# wiiceiver_v2.net
KiCad netlist of a schematic drawn in EAGLE
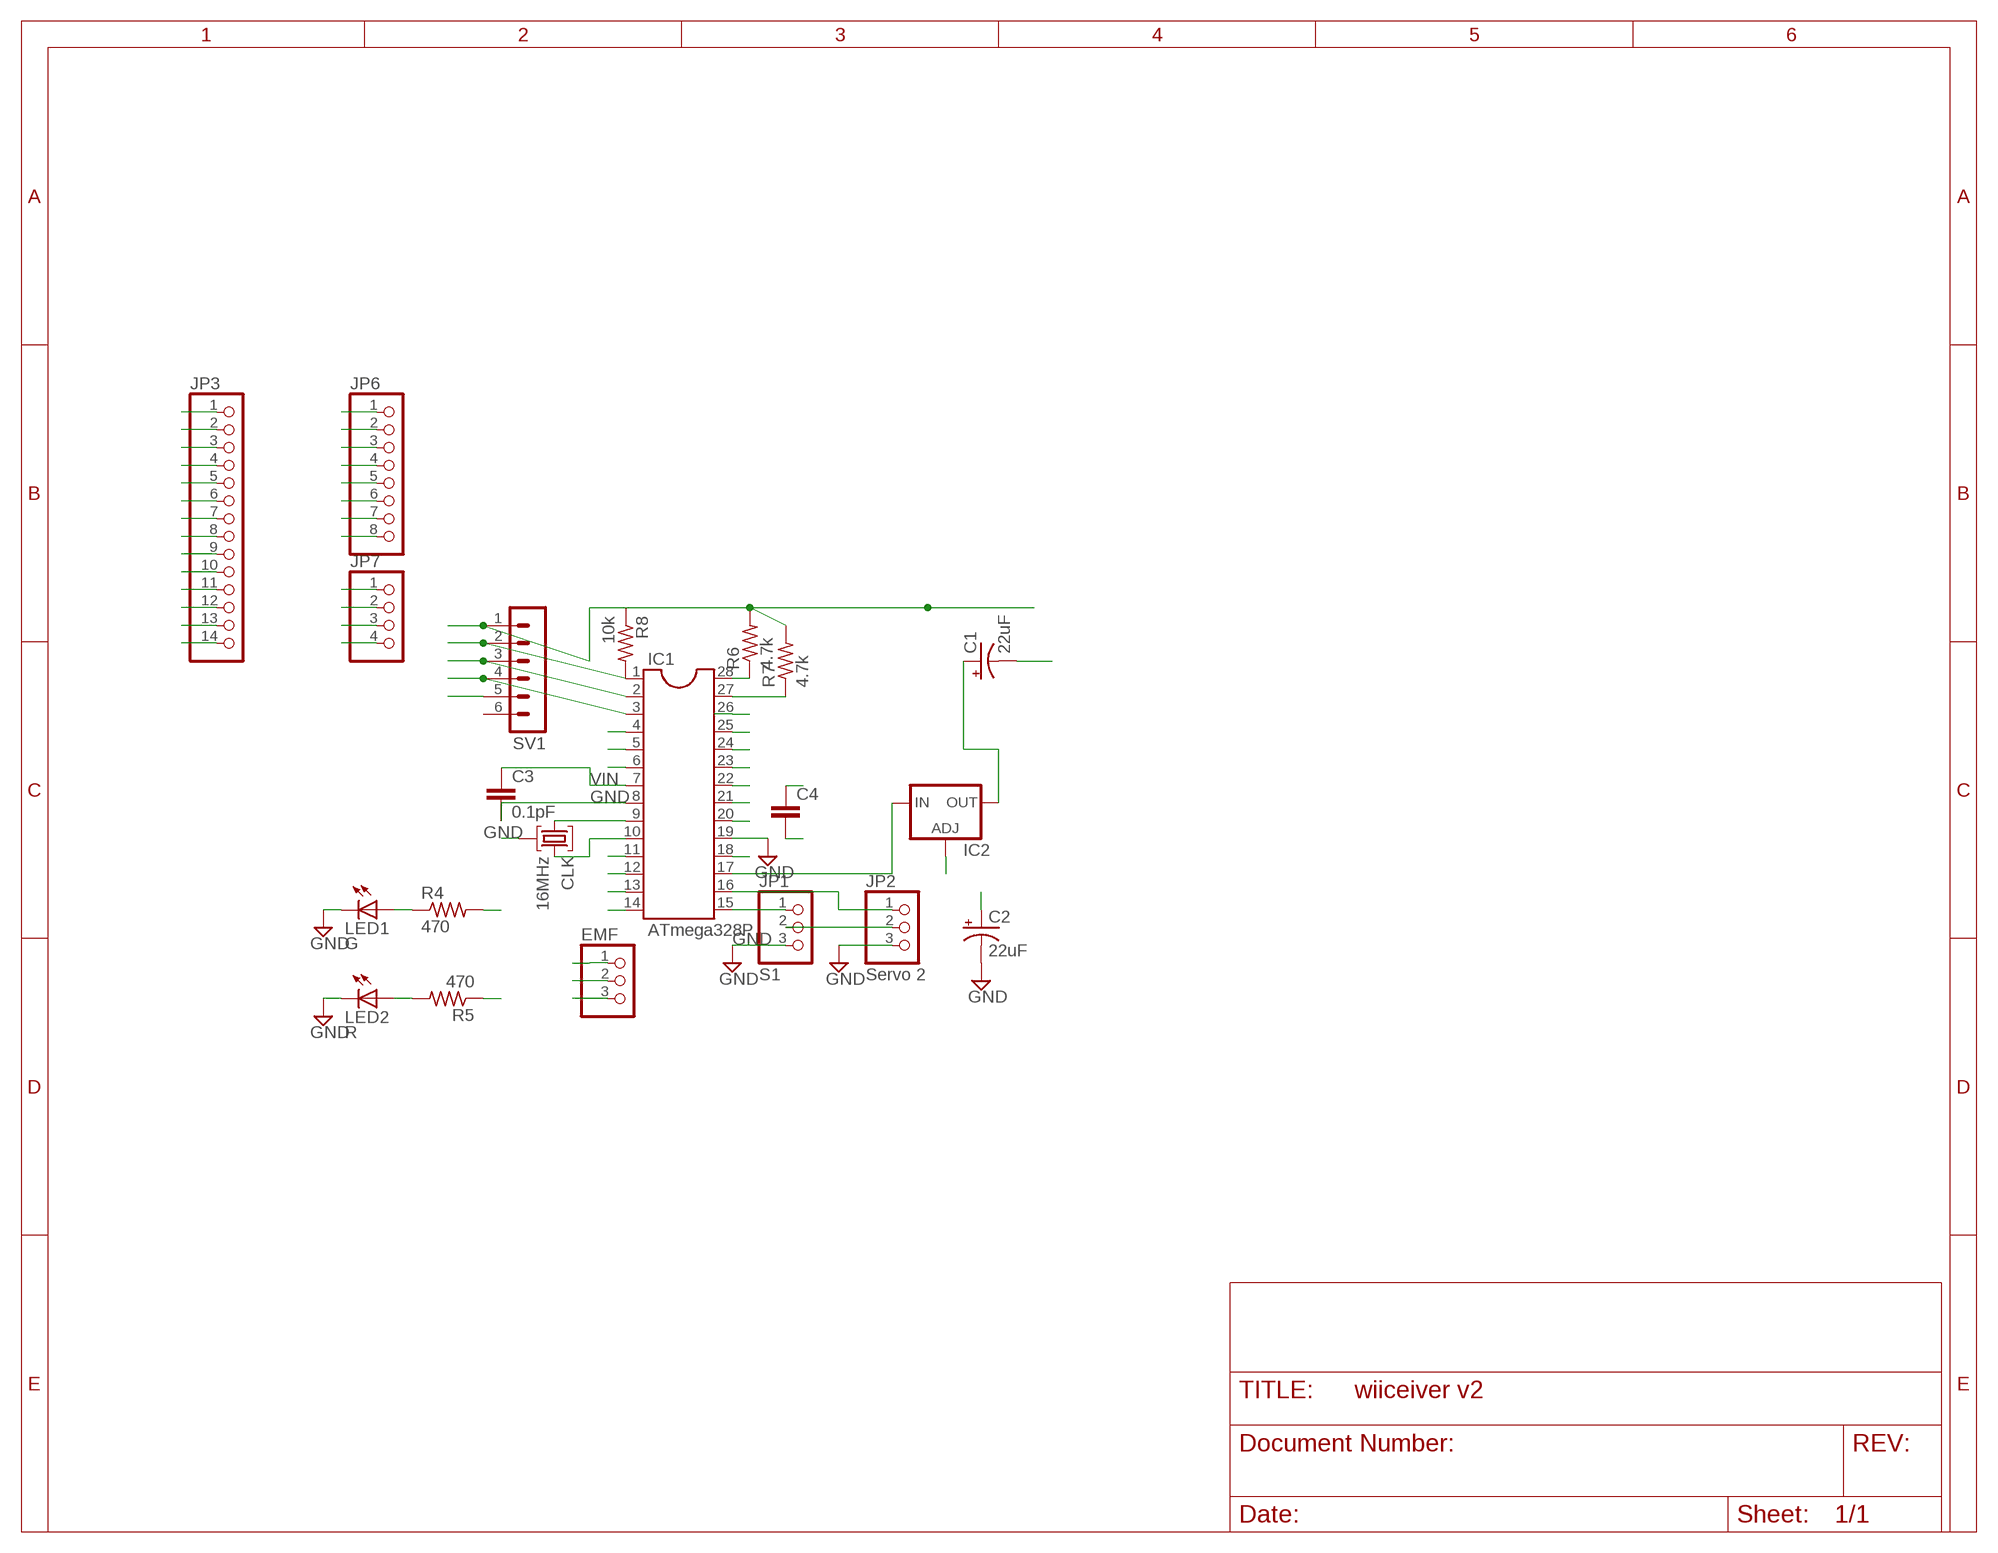
[diagram p0: schematic, sheet 1]

(export (version "E")
  (design (tool "Eeschema 10.0.6"))
  (components
    (comp (ref "C1")
      (value "22uF")
      (footprint "eagle-import:B45181A")
      (libsource (lib "eagle-import") (part "CPOL-USB45181A"))
    )
    (comp (ref "C2")
      (value "22uF")
      (footprint "eagle-import:B45181A")
      (libsource (lib "eagle-import") (part "CPOL-USB45181A"))
    )
    (comp (ref "C3")
      (value "0.1pF")
      (footprint "eagle-import:C5B2.5")
      (libsource (lib "eagle-import") (part "C5/2.5"))
    )
    (comp (ref "C4")
      (value "C5/2.5")
      (footprint "eagle-import:C5B2.5")
      (libsource (lib "eagle-import") (part "C5/2.5"))
    )
    (comp (ref "CLK")
      (value "16MHz")
      (footprint "eagle-import:HC49U")
      (libsource (lib "eagle-import") (part "IXFA"))
    )
    (comp (ref "EMF")
      (value "PINHD-1X3")
      (footprint "eagle-import:1X03")
      (libsource (lib "eagle-import") (part "PINHD-1X3"))
    )
    (comp (ref "IC1")
      (value "ATmega328P")
      (footprint "eagle-import:DIL28-3")
      (libsource (lib "eagle-import") (part "DIL28-3"))
    )
    (comp (ref "IC2")
      (value "LM317TS")
      (footprint "eagle-import:317TS")
      (libsource (lib "eagle-import") (part "LM317TS"))
    )
    (comp (ref "JP1")
      (value "S1")
      (footprint "eagle-import:1X03")
      (libsource (lib "eagle-import") (part "PINHD-1X3"))
    )
    (comp (ref "JP2")
      (value "Servo 2")
      (footprint "eagle-import:1X03")
      (libsource (lib "eagle-import") (part "PINHD-1X3"))
    )
    (comp (ref "JP3")
      (value "PINHD-1X14")
      (footprint "eagle-import:1X14")
      (libsource (lib "eagle-import") (part "PINHD-1X14"))
    )
    (comp (ref "JP6")
      (value "PINHD-1X8")
      (footprint "eagle-import:1X08")
      (libsource (lib "eagle-import") (part "PINHD-1X8"))
    )
    (comp (ref "JP7")
      (value "PINHD-1X4")
      (footprint "eagle-import:1X04")
      (libsource (lib "eagle-import") (part "PINHD-1X4"))
    )
    (comp (ref "LED1")
      (value "G")
      (footprint "eagle-import:LED3MM")
      (libsource (lib "eagle-import") (part "LED3MM"))
    )
    (comp (ref "LED2")
      (value "R")
      (footprint "eagle-import:LED3MM")
      (libsource (lib "eagle-import") (part "LED3MM"))
    )
    (comp (ref "R4")
      (value "470")
      (footprint "eagle-import:0204V")
      (libsource (lib "eagle-import") (part "R-US_0204/2V"))
    )
    (comp (ref "R5")
      (value "470")
      (footprint "eagle-import:0204V")
      (libsource (lib "eagle-import") (part "R-US_0204/2V"))
    )
    (comp (ref "R6")
      (value "4.7k")
      (footprint "eagle-import:0204V")
      (libsource (lib "eagle-import") (part "R-US_0204/2V"))
    )
    (comp (ref "R7")
      (value "4.7k")
      (footprint "eagle-import:0204V")
      (libsource (lib "eagle-import") (part "R-US_0204/2V"))
    )
    (comp (ref "R8")
      (value "10k")
      (footprint "eagle-import:0204V")
      (libsource (lib "eagle-import") (part "R-US_0204/2V"))
    )
    (comp (ref "SV1")
      (value "MA06-1")
      (footprint "eagle-import:MA06-1")
      (libsource (lib "eagle-import") (part "MA06-1"))
    )
  )
  (nets
    (net (code "1") (name "/A0") (class "Default")
      (node (ref "IC1") (pin "23") (pinfunction "23_23") (pintype "passive"))
      (node (ref "JP3") (pin "6") (pinfunction "6_6") (pintype "passive"))
    )
    (net (code "2") (name "/A1") (class "Default")
      (node (ref "IC1") (pin "24") (pinfunction "24_24") (pintype "passive"))
      (node (ref "JP3") (pin "5") (pinfunction "5_5") (pintype "passive"))
    )
    (net (code "3") (name "/A2") (class "Default")
      (node (ref "IC1") (pin "25") (pinfunction "25_25") (pintype "passive"))
      (node (ref "JP3") (pin "4") (pinfunction "4_4") (pintype "passive"))
    )
    (net (code "4") (name "/A3") (class "Default")
      (node (ref "IC1") (pin "26") (pinfunction "26_26") (pintype "passive"))
      (node (ref "JP3") (pin "3") (pinfunction "3_3") (pintype "passive"))
    )
    (net (code "5") (name "/A4") (class "Default")
      (node (ref "IC1") (pin "27") (pinfunction "27_27") (pintype "passive"))
      (node (ref "JP3") (pin "2") (pinfunction "2_2") (pintype "passive"))
      (node (ref "R7") (pin "1") (pinfunction "1_1") (pintype "passive"))
    )
    (net (code "6") (name "/A5") (class "Default")
      (node (ref "IC1") (pin "28") (pinfunction "28_28") (pintype "passive"))
      (node (ref "JP3") (pin "1") (pinfunction "1_1") (pintype "passive"))
      (node (ref "R6") (pin "1") (pinfunction "1_1") (pintype "passive"))
    )
    (net (code "7") (name "/D0") (class "Default")
      (node (ref "IC1") (pin "2") (pinfunction "2_2") (pintype "passive"))
      (node (ref "JP6") (pin "2") (pinfunction "2_2") (pintype "passive"))
      (node (ref "SV1") (pin "3") (pinfunction "3_3") (pintype "passive"))
    )
    (net (code "8") (name "/D1") (class "Default")
      (node (ref "IC1") (pin "3") (pinfunction "3_3") (pintype "passive"))
      (node (ref "JP6") (pin "3") (pinfunction "3_3") (pintype "passive"))
      (node (ref "SV1") (pin "4") (pinfunction "4_4") (pintype "passive"))
    )
    (net (code "9") (name "/D2") (class "Default")
      (node (ref "IC1") (pin "4") (pinfunction "4_4") (pintype "passive"))
      (node (ref "JP6") (pin "4") (pinfunction "4_4") (pintype "passive"))
    )
    (net (code "10") (name "/D3") (class "Default")
      (node (ref "IC1") (pin "5") (pinfunction "5_5") (pintype "passive"))
      (node (ref "JP6") (pin "5") (pinfunction "5_5") (pintype "passive"))
    )
    (net (code "11") (name "/D4") (class "Default")
      (node (ref "IC1") (pin "6") (pinfunction "6_6") (pintype "passive"))
      (node (ref "JP6") (pin "6") (pinfunction "6_6") (pintype "passive"))
    )
    (net (code "12") (name "/D5") (class "Default")
      (node (ref "IC1") (pin "11") (pinfunction "11_11") (pintype "passive"))
      (node (ref "JP7") (pin "1") (pinfunction "1_1") (pintype "passive"))
    )
    (net (code "13") (name "/D6") (class "Default")
      (node (ref "IC1") (pin "12") (pinfunction "12_12") (pintype "passive"))
      (node (ref "JP7") (pin "2") (pinfunction "2_2") (pintype "passive"))
      (node (ref "R4") (pin "2") (pinfunction "2_2") (pintype "passive"))
    )
    (net (code "14") (name "/D7") (class "Default")
      (node (ref "IC1") (pin "13") (pinfunction "13_13") (pintype "passive"))
      (node (ref "JP7") (pin "3") (pinfunction "3_3") (pintype "passive"))
    )
    (net (code "15") (name "/D8") (class "Default")
      (node (ref "IC1") (pin "14") (pinfunction "14_14") (pintype "passive"))
      (node (ref "JP7") (pin "4") (pinfunction "4_4") (pintype "passive"))
      (node (ref "R5") (pin "1") (pinfunction "1_1") (pintype "passive"))
    )
    (net (code "16") (name "/D9") (class "Default")
      (node (ref "IC1") (pin "15") (pinfunction "15_15") (pintype "passive"))
      (node (ref "JP1") (pin "1") (pinfunction "1_1") (pintype "passive"))
      (node (ref "JP3") (pin "14") (pinfunction "14_14") (pintype "passive"))
    )
    (net (code "17") (name "/D10") (class "Default")
      (node (ref "IC1") (pin "16") (pinfunction "16_16") (pintype "passive"))
      (node (ref "JP2") (pin "1") (pinfunction "1_1") (pintype "passive"))
      (node (ref "JP3") (pin "13") (pinfunction "13_13") (pintype "passive"))
    )
    (net (code "18") (name "/D11") (class "Default")
      (node (ref "IC1") (pin "17") (pinfunction "17_17") (pintype "passive"))
      (node (ref "IC2") (pin "3") (pinfunction "IN_3") (pintype "input"))
      (node (ref "JP3") (pin "12") (pinfunction "12_12") (pintype "passive"))
    )
    (net (code "19") (name "/D12") (class "Default")
      (node (ref "IC1") (pin "18") (pinfunction "18_18") (pintype "passive"))
      (node (ref "JP3") (pin "11") (pinfunction "11_11") (pintype "passive"))
    )
    (net (code "20") (name "/RST") (class "Default")
      (node (ref "IC1") (pin "1") (pinfunction "1_1") (pintype "passive"))
      (node (ref "JP6") (pin "1") (pinfunction "1_1") (pintype "passive"))
      (node (ref "R8") (pin "2") (pinfunction "2_2") (pintype "passive"))
      (node (ref "SV1") (pin "2") (pinfunction "2_2") (pintype "passive"))
    )
    (net (code "21") (name "/VIN") (class "Default")
      (node (ref "C3") (pin "1") (pinfunction "1_1") (pintype "passive"))
      (node (ref "C4") (pin "1") (pinfunction "1_1") (pintype "passive"))
      (node (ref "EMF") (pin "3") (pinfunction "3_3") (pintype "passive"))
      (node (ref "IC1") (pin "20") (pinfunction "20_20") (pintype "passive"))
      (node (ref "IC1") (pin "21") (pinfunction "21_21") (pintype "passive"))
      (node (ref "IC1") (pin "7") (pinfunction "7_7") (pintype "passive"))
      (node (ref "JP3") (pin "8") (pinfunction "8_8") (pintype "passive"))
      (node (ref "JP3") (pin "9") (pinfunction "9_9") (pintype "passive"))
      (node (ref "JP6") (pin "7") (pinfunction "7_7") (pintype "passive"))
      (node (ref "R6") (pin "2") (pinfunction "2_2") (pintype "passive"))
      (node (ref "R7") (pin "2") (pinfunction "2_2") (pintype "passive"))
      (node (ref "R8") (pin "1") (pinfunction "1_1") (pintype "passive"))
      (node (ref "SV1") (pin "1") (pinfunction "1_1") (pintype "passive"))
    )
    (net (code "22") (name "/VRAW") (class "Default")
      (node (ref "C2") (pin "+") (pinfunction "+_+") (pintype "passive"))
      (node (ref "EMF") (pin "1") (pinfunction "1_1") (pintype "passive"))
      (node (ref "JP1") (pin "2") (pinfunction "2_2") (pintype "passive"))
      (node (ref "JP2") (pin "2") (pinfunction "2_2") (pintype "passive"))
    )
    (net (code "23") (name "GND") (class "Default")
      (node (ref "C1") (pin "-") (pinfunction "-_-") (pintype "passive"))
      (node (ref "C2") (pin "-") (pinfunction "-_-") (pintype "passive"))
      (node (ref "C3") (pin "2") (pinfunction "2_2") (pintype "passive"))
      (node (ref "C4") (pin "2") (pinfunction "2_2") (pintype "passive"))
      (node (ref "CLK") (pin "2") (pinfunction "2_2") (pintype "passive"))
      (node (ref "EMF") (pin "2") (pinfunction "2_2") (pintype "passive"))
      (node (ref "IC1") (pin "19") (pinfunction "19_19") (pintype "passive"))
      (node (ref "IC1") (pin "22") (pinfunction "22_22") (pintype "passive"))
      (node (ref "IC1") (pin "8") (pinfunction "8_8") (pintype "passive"))
      (node (ref "IC2") (pin "1") (pinfunction "ADJ_1") (pintype "input"))
      (node (ref "JP1") (pin "3") (pinfunction "3_3") (pintype "passive"))
      (node (ref "JP2") (pin "3") (pinfunction "3_3") (pintype "passive"))
      (node (ref "JP3") (pin "7") (pinfunction "7_7") (pintype "passive"))
      (node (ref "JP6") (pin "8") (pinfunction "8_8") (pintype "passive"))
      (node (ref "LED1") (pin "K") (pinfunction "C_K") (pintype "passive"))
      (node (ref "LED2") (pin "K") (pinfunction "C_K") (pintype "passive"))
      (node (ref "SV1") (pin "5") (pinfunction "5_5") (pintype "passive"))
    )
    (net (code "24") (name "Net-(CLK-Pad1)") (class "Default")
      (node (ref "CLK") (pin "1") (pinfunction "1_1") (pintype "passive"))
      (node (ref "IC1") (pin "9") (pinfunction "9_9") (pintype "passive"))
    )
    (net (code "25") (name "Net-(CLK-Pad3)") (class "Default")
      (node (ref "CLK") (pin "3") (pinfunction "3_3") (pintype "passive"))
      (node (ref "IC1") (pin "10") (pinfunction "10_10") (pintype "passive"))
    )
    (net (code "26") (name "Net-(IC2-OUT)") (class "Default")
      (node (ref "C1") (pin "+") (pinfunction "+_+") (pintype "passive"))
      (node (ref "IC2") (pin "2") (pinfunction "OUT_2") (pintype "passive"))
    )
    (net (code "27") (name "Net-(LED1-PadA)") (class "Default")
      (node (ref "LED1") (pin "A") (pinfunction "A_A") (pintype "passive"))
      (node (ref "R4") (pin "1") (pinfunction "1_1") (pintype "passive"))
    )
    (net (code "28") (name "Net-(LED2-PadA)") (class "Default")
      (node (ref "LED2") (pin "A") (pinfunction "A_A") (pintype "passive"))
      (node (ref "R5") (pin "2") (pinfunction "2_2") (pintype "passive"))
    )
    (net (code "29") (name "unconnected-(JP3-Pad10)") (class "Default")
      (node (ref "JP3") (pin "10") (pinfunction "10_10") (pintype "passive"))
    )
    (net (code "30") (name "unconnected-(SV1-Pad6)") (class "Default")
      (node (ref "SV1") (pin "6") (pinfunction "6_6") (pintype "passive"))
    )
  )
)
